# ESP8266_MegaD_v0_9.net
KiCad netlist of a schematic drawn in EAGLE
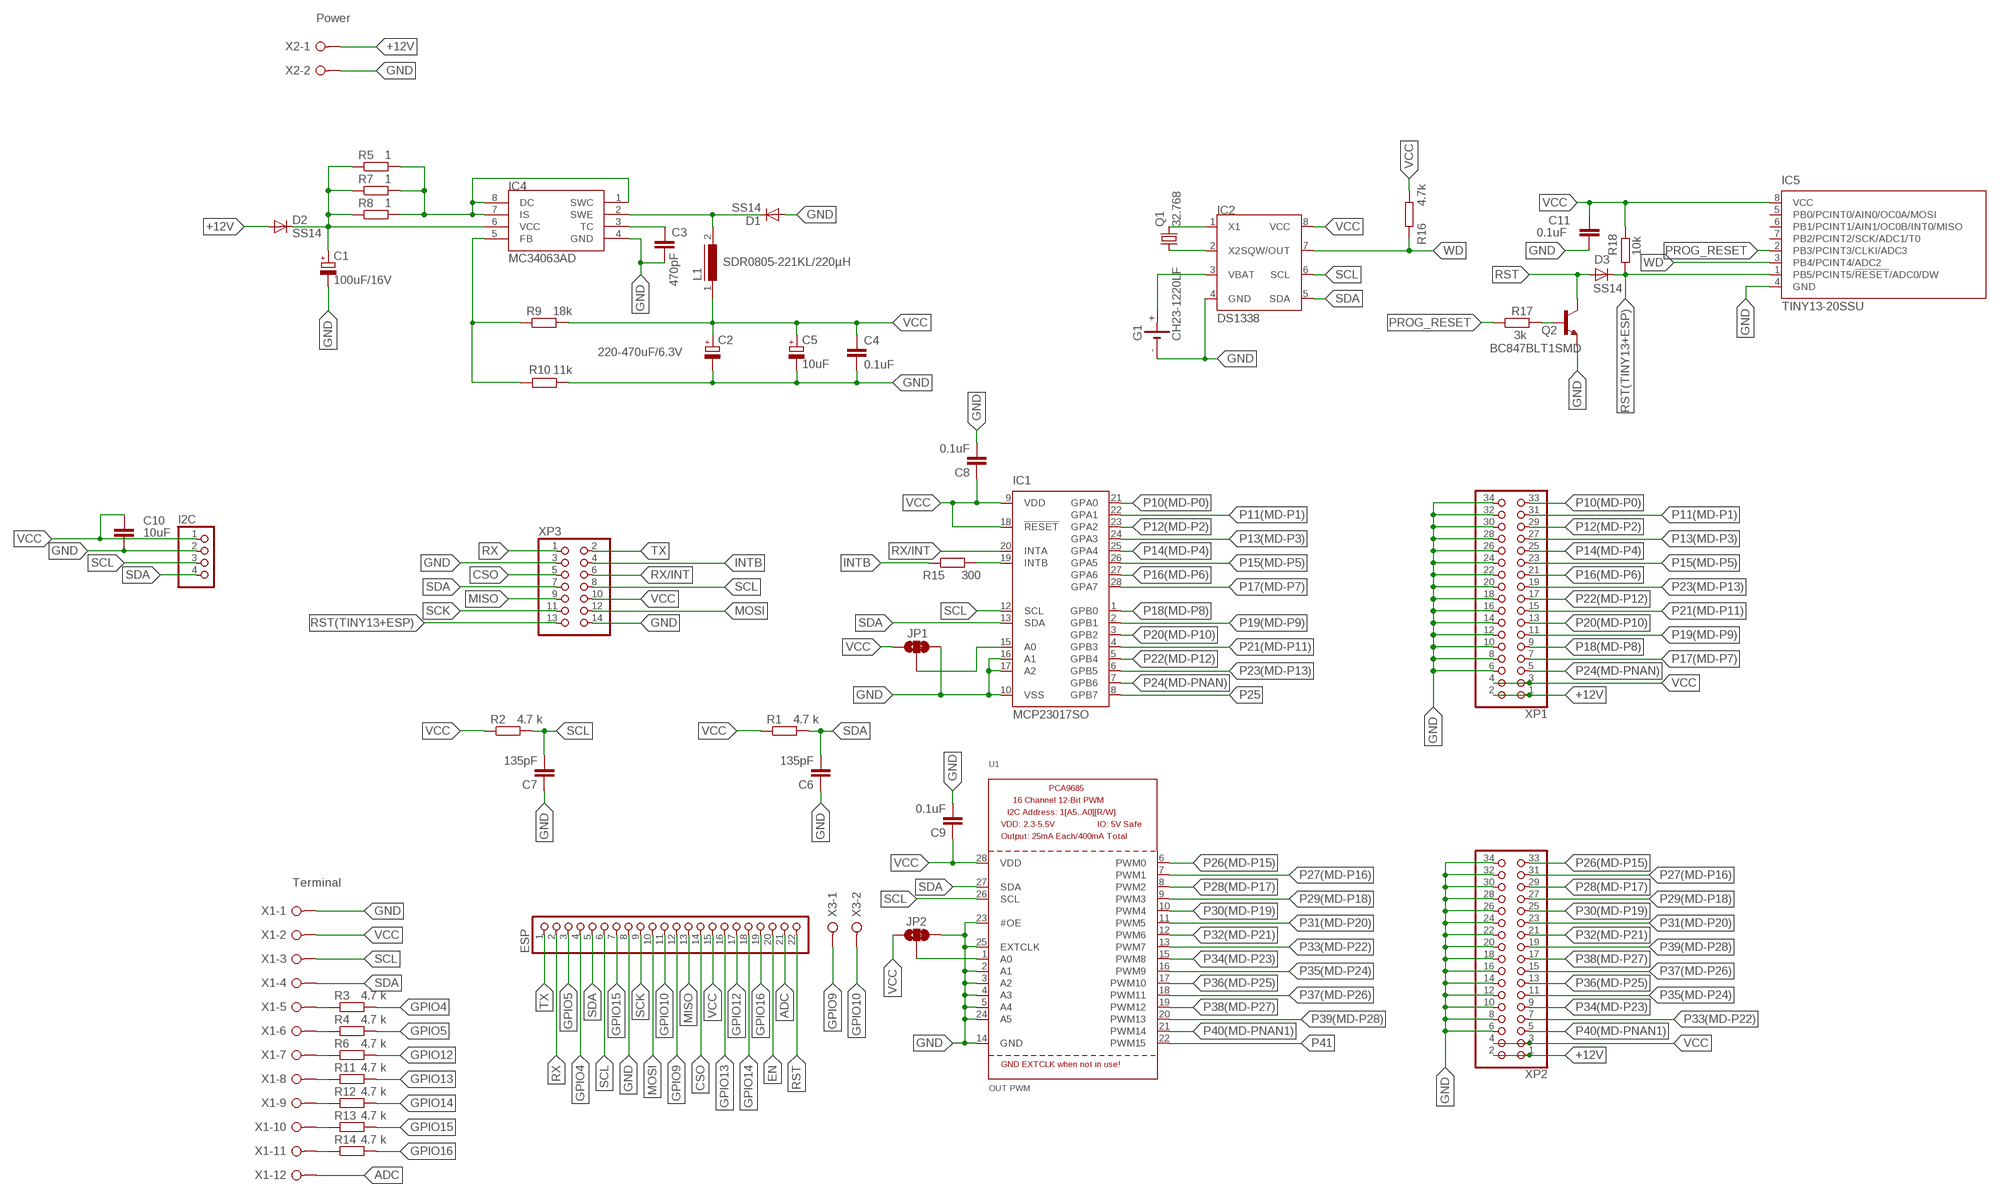
[diagram p0: schematic, sheet 1]

(export (version "E")
  (design (tool "Eeschema 10.0.6"))
  (components
    (comp (ref "C1")
      (value "100uF/16V")
      (footprint "eagle-import:140CLH-0810")
      (libsource (lib "eagle-import") (part "CPOL-EU140CLH-0810"))
    )
    (comp (ref "C2")
      (value "220-470uF/6.3V")
      (footprint "eagle-import:140CLH-0810")
      (libsource (lib "eagle-import") (part "CPOL-EU140CLH-0810"))
    )
    (comp (ref "C3")
      (value "470pF")
      (footprint "eagle-import:C1206")
      (libsource (lib "eagle-import") (part "C-EUC1206"))
    )
    (comp (ref "C4")
      (value "0.1uF")
      (footprint "eagle-import:C1206")
      (libsource (lib "eagle-import") (part "C-EUC1206"))
    )
    (comp (ref "C5")
      (value "10uF")
      (footprint "eagle-import:C_6032-28R")
      (libsource (lib "eagle-import") (part "CPOL-EUC/6032-28R"))
    )
    (comp (ref "C6")
      (value "135pF")
      (footprint "eagle-import:C1206")
      (libsource (lib "eagle-import") (part "C-EUC1206"))
    )
    (comp (ref "C7")
      (value "135pF")
      (footprint "eagle-import:C1206")
      (libsource (lib "eagle-import") (part "C-EUC1206"))
    )
    (comp (ref "C8")
      (value "0.1uF")
      (footprint "eagle-import:C1206")
      (libsource (lib "eagle-import") (part "C-EUC1206"))
    )
    (comp (ref "C9")
      (value "0.1uF")
      (footprint "eagle-import:C1206")
      (libsource (lib "eagle-import") (part "C-EUC1206"))
    )
    (comp (ref "C10")
      (value "10uF")
      (footprint "eagle-import:C1206")
      (libsource (lib "eagle-import") (part "C-EUC1206"))
    )
    (comp (ref "C11")
      (value "0.1uF")
      (footprint "eagle-import:C1206")
      (libsource (lib "eagle-import") (part "C-EUC1206"))
    )
    (comp (ref "D1")
      (value "SS14")
      (footprint "eagle-import:SMA")
      (libsource (lib "eagle-import") (part "S1M"))
    )
    (comp (ref "D2")
      (value "SS14")
      (footprint "eagle-import:SMA")
      (libsource (lib "eagle-import") (part "S1M"))
    )
    (comp (ref "D3")
      (value "SS14")
      (footprint "eagle-import:SMA")
      (libsource (lib "eagle-import") (part "S1M"))
    )
    (comp (ref "ESP")
      (value "PINHD-1X22")
      (footprint "eagle-import:1X22")
      (libsource (lib "eagle-import") (part "PINHD-1X22"))
    )
    (comp (ref "G1")
      (value "CH23-1220LF")
      (footprint "eagle-import:CH23-1220LF")
      (libsource (lib "eagle-import") (part "CH23-1220LF"))
    )
    (comp (ref "I2C")
      (value "PINHD-1X4")
      (footprint "eagle-import:1X04")
      (libsource (lib "eagle-import") (part "PINHD-1X4"))
    )
    (comp (ref "IC1")
      (value "MCP23017SO")
      (footprint "eagle-import:SO28W")
      (fields (field (name "MF") "MICROCHIP") (field (name "MPN") "MCP23017-E/SO"))
      (libsource (lib "eagle-import") (part "MCP23017SO"))
    )
    (comp (ref "IC2")
      (value "DS1338")
      (footprint "eagle-import:SOIC-8")
      (libsource (lib "eagle-import") (part "DS1307"))
    )
    (comp (ref "IC4")
      (value "MC34063AD")
      (footprint "eagle-import:SOIC8")
      (libsource (lib "eagle-import") (part "MC34063AD"))
    )
    (comp (ref "IC5")
      (value "TINY13-20SSU")
      (footprint "eagle-import:8S1")
      (fields (field (name "MPN") "ATTINY13-20SSU"))
      (libsource (lib "eagle-import") (part "TINY13SSU-20"))
    )
    (comp (ref "JP1")
      (value "JUMPER-PAD-3-2OF3_NC_BY_TRACE_LARGE")
      (footprint "eagle-import:PAD-JUMPER-3-2OF3_NC_BY_TRACE_YES_SILK_LARGE")
      (libsource (lib "eagle-import") (part "JUMPER-PAD-3-2OF3_NC_BY_TRACE_LARGE"))
    )
    (comp (ref "JP2")
      (value "JUMPER-PAD-3-2OF3_NC_BY_TRACE_LARGE")
      (footprint "eagle-import:PAD-JUMPER-3-2OF3_NC_BY_TRACE_YES_SILK_LARGE")
      (libsource (lib "eagle-import") (part "JUMPER-PAD-3-2OF3_NC_BY_TRACE_LARGE"))
    )
    (comp (ref "L1")
      (value "SDR0805-221KL/220µH")
      (footprint "eagle-import:DR73")
      (libsource (lib "eagle-import") (part "DR73"))
    )
    (comp (ref "Q1")
      (value "32.768")
      (footprint "eagle-import:TC38H")
      (libsource (lib "eagle-import") (part "CRYSTALTC38H"))
    )
    (comp (ref "Q2")
      (value "BC847BLT1SMD")
      (footprint "eagle-import:SOT23")
      (libsource (lib "eagle-import") (part "BC847SMDBLT1"))
    )
    (comp (ref "R1")
      (value "4.7 k")
      (footprint "eagle-import:R1206")
      (libsource (lib "eagle-import") (part "R-EU_R1206"))
    )
    (comp (ref "R2")
      (value "4.7 k")
      (footprint "eagle-import:R1206")
      (libsource (lib "eagle-import") (part "R-EU_R1206"))
    )
    (comp (ref "R3")
      (value "4.7 k")
      (footprint "eagle-import:R1206")
      (libsource (lib "eagle-import") (part "R-EU_R1206"))
    )
    (comp (ref "R4")
      (value "4.7 k")
      (footprint "eagle-import:R1206")
      (libsource (lib "eagle-import") (part "R-EU_R1206"))
    )
    (comp (ref "R5")
      (value "1")
      (footprint "eagle-import:R1206")
      (libsource (lib "eagle-import") (part "R-EU_R1206"))
    )
    (comp (ref "R6")
      (value "4.7 k")
      (footprint "eagle-import:R1206")
      (libsource (lib "eagle-import") (part "R-EU_R1206"))
    )
    (comp (ref "R7")
      (value "1")
      (footprint "eagle-import:R1206")
      (libsource (lib "eagle-import") (part "R-EU_R1206"))
    )
    (comp (ref "R8")
      (value "1")
      (footprint "eagle-import:R1206")
      (libsource (lib "eagle-import") (part "R-EU_R1206"))
    )
    (comp (ref "R9")
      (value "18k")
      (footprint "eagle-import:R1206")
      (libsource (lib "eagle-import") (part "R-EU_R1206"))
    )
    (comp (ref "R10")
      (value "11k")
      (footprint "eagle-import:R1206")
      (libsource (lib "eagle-import") (part "R-EU_R1206"))
    )
    (comp (ref "R11")
      (value "4.7 k")
      (footprint "eagle-import:R1206")
      (libsource (lib "eagle-import") (part "R-EU_R1206"))
    )
    (comp (ref "R12")
      (value "4.7 k")
      (footprint "eagle-import:R1206")
      (libsource (lib "eagle-import") (part "R-EU_R1206"))
    )
    (comp (ref "R13")
      (value "4.7 k")
      (footprint "eagle-import:R1206")
      (libsource (lib "eagle-import") (part "R-EU_R1206"))
    )
    (comp (ref "R14")
      (value "4.7 k")
      (footprint "eagle-import:R1206")
      (libsource (lib "eagle-import") (part "R-EU_R1206"))
    )
    (comp (ref "R15")
      (value "300")
      (footprint "eagle-import:R1206")
      (libsource (lib "eagle-import") (part "R-EU_R1206"))
    )
    (comp (ref "R16")
      (value "4.7k")
      (footprint "eagle-import:R1206")
      (libsource (lib "eagle-import") (part "R-EU_R1206"))
    )
    (comp (ref "R17")
      (value "3k")
      (footprint "eagle-import:R1206")
      (libsource (lib "eagle-import") (part "R-EU_R1206"))
    )
    (comp (ref "R18")
      (value "10k")
      (footprint "eagle-import:R1206")
      (libsource (lib "eagle-import") (part "R-EU_R1206"))
    )
    (comp (ref "U1")
      (value "OUT PWM")
      (footprint "eagle-import:TSSOP28")
      (libsource (lib "eagle-import") (part "PCA9685"))
    )
    (comp (ref "X1")
      (value "Terminal")
      (footprint "eagle-import:W237-12P")
      (libsource (lib "eagle-import") (part "W237-12P"))
    )
    (comp (ref "X2")
      (value "Power")
      (footprint "eagle-import:W237-132")
      (libsource (lib "eagle-import") (part "W237-02P"))
    )
    (comp (ref "X3")
      (value "W237-02P")
      (footprint "eagle-import:W237-132")
      (libsource (lib "eagle-import") (part "W237-02P"))
    )
    (comp (ref "XP1")
      (value "PINHD-2X17/90")
      (footprint "eagle-import:2X17_90")
      (libsource (lib "eagle-import") (part "PINHD-2X17/90"))
    )
    (comp (ref "XP2")
      (value "PINHD-2X17")
      (footprint "eagle-import:2X17")
      (libsource (lib "eagle-import") (part "PINHD-2X17"))
    )
    (comp (ref "XP3")
      (value "PINHD-2X7")
      (footprint "eagle-import:2X07")
      (libsource (lib "eagle-import") (part "PINHD-2X7"))
    )
  )
  (nets
    (net (code "1") (name "+12V") (class "Default")
      (node (ref "D2") (pin "A") (pinfunction "A_A") (pintype "passive"))
      (node (ref "X2") (pin "1") (pinfunction "KL_1") (pintype "passive"))
      (node (ref "XP1") (pin "1") (pinfunction "1_1") (pintype "passive"))
      (node (ref "XP1") (pin "2") (pinfunction "2_2") (pintype "passive"))
      (node (ref "XP2") (pin "1") (pinfunction "1_1") (pintype "passive"))
      (node (ref "XP2") (pin "2") (pinfunction "2_2") (pintype "passive"))
    )
    (net (code "2") (name "ADC") (class "Default")
      (node (ref "ESP") (pin "21") (pinfunction "21_21") (pintype "passive"))
      (node (ref "X1") (pin "12") (pinfunction "KL_12") (pintype "passive"))
    )
    (net (code "3") (name "CSO") (class "Default")
      (node (ref "ESP") (pin "14") (pinfunction "14_14") (pintype "passive"))
      (node (ref "XP3") (pin "5") (pinfunction "5_5") (pintype "passive"))
    )
    (net (code "4") (name "EN") (class "Default")
      (node (ref "ESP") (pin "20") (pinfunction "20_20") (pintype "passive"))
    )
    (net (code "5") (name "GND") (class "Default")
      (node (ref "C1") (pin "-") (pinfunction "-_-") (pintype "passive"))
      (node (ref "C10") (pin "1") (pinfunction "1_1") (pintype "passive"))
      (node (ref "C11") (pin "2") (pinfunction "2_2") (pintype "passive"))
      (node (ref "C2") (pin "-") (pinfunction "-_-") (pintype "passive"))
      (node (ref "C3") (pin "2") (pinfunction "2_2") (pintype "passive"))
      (node (ref "C4") (pin "2") (pinfunction "2_2") (pintype "passive"))
      (node (ref "C5") (pin "-") (pinfunction "-_-") (pintype "passive"))
      (node (ref "C6") (pin "1") (pinfunction "1_1") (pintype "passive"))
      (node (ref "C7") (pin "1") (pinfunction "1_1") (pintype "passive"))
      (node (ref "C8") (pin "2") (pinfunction "2_2") (pintype "passive"))
      (node (ref "C9") (pin "2") (pinfunction "2_2") (pintype "passive"))
      (node (ref "D1") (pin "A") (pinfunction "A_A") (pintype "passive"))
      (node (ref "ESP") (pin "8") (pinfunction "8_8") (pintype "passive"))
      (node (ref "G1") (pin "-") (pinfunction "-_-") (pintype "passive"))
      (node (ref "I2C") (pin "2") (pinfunction "2_2") (pintype "passive"))
      (node (ref "IC1") (pin "10") (pinfunction "VSS_10") (pintype "power_in"))
      (node (ref "IC1") (pin "16") (pinfunction "A1_16") (pintype "input"))
      (node (ref "IC1") (pin "17") (pinfunction "A2_17") (pintype "input"))
      (node (ref "IC2") (pin "4") (pinfunction "GND_4") (pintype "power_in"))
      (node (ref "IC4") (pin "4") (pinfunction "GND_4") (pintype "passive"))
      (node (ref "IC5") (pin "4") (pinfunction "GND_4") (pintype "power_in"))
      (node (ref "JP1") (pin "3") (pinfunction "3_3") (pintype "passive"))
      (node (ref "JP2") (pin "3") (pinfunction "3_3") (pintype "passive"))
      (node (ref "Q2") (pin "2") (pinfunction "E_2") (pintype "passive"))
      (node (ref "R10") (pin "1") (pinfunction "1_1") (pintype "passive"))
      (node (ref "U1") (pin "14") (pinfunction "GND_14") (pintype "power_in"))
      (node (ref "U1") (pin "2") (pinfunction "A1_2") (pintype "bidirectional"))
      (node (ref "U1") (pin "23") (pinfunction "#OE_23") (pintype "input"))
      (node (ref "U1") (pin "24") (pinfunction "A5_24") (pintype "bidirectional"))
      (node (ref "U1") (pin "25") (pinfunction "EXTCLK_25") (pintype "input"))
      (node (ref "U1") (pin "3") (pinfunction "A2_3") (pintype "bidirectional"))
      (node (ref "U1") (pin "4") (pinfunction "A3_4") (pintype "bidirectional"))
      (node (ref "U1") (pin "5") (pinfunction "A4_5") (pintype "bidirectional"))
      (node (ref "X1") (pin "1") (pinfunction "KL_1") (pintype "passive"))
      (node (ref "X2") (pin "2") (pinfunction "KL_2") (pintype "passive"))
      (node (ref "XP1") (pin "10") (pinfunction "10_10") (pintype "passive"))
      (node (ref "XP1") (pin "12") (pinfunction "12_12") (pintype "passive"))
      (node (ref "XP1") (pin "14") (pinfunction "14_14") (pintype "passive"))
      (node (ref "XP1") (pin "16") (pinfunction "16_16") (pintype "passive"))
      (node (ref "XP1") (pin "18") (pinfunction "18_18") (pintype "passive"))
      (node (ref "XP1") (pin "20") (pinfunction "20_20") (pintype "passive"))
      (node (ref "XP1") (pin "22") (pinfunction "22_22") (pintype "passive"))
      (node (ref "XP1") (pin "24") (pinfunction "24_24") (pintype "passive"))
      (node (ref "XP1") (pin "26") (pinfunction "26_26") (pintype "passive"))
      (node (ref "XP1") (pin "28") (pinfunction "28_28") (pintype "passive"))
      (node (ref "XP1") (pin "30") (pinfunction "30_30") (pintype "passive"))
      (node (ref "XP1") (pin "32") (pinfunction "32_32") (pintype "passive"))
      (node (ref "XP1") (pin "34") (pinfunction "34_34") (pintype "passive"))
      (node (ref "XP1") (pin "6") (pinfunction "6_6") (pintype "passive"))
      (node (ref "XP1") (pin "8") (pinfunction "8_8") (pintype "passive"))
      (node (ref "XP2") (pin "10") (pinfunction "10_10") (pintype "passive"))
      (node (ref "XP2") (pin "12") (pinfunction "12_12") (pintype "passive"))
      (node (ref "XP2") (pin "14") (pinfunction "14_14") (pintype "passive"))
      (node (ref "XP2") (pin "16") (pinfunction "16_16") (pintype "passive"))
      (node (ref "XP2") (pin "18") (pinfunction "18_18") (pintype "passive"))
      (node (ref "XP2") (pin "20") (pinfunction "20_20") (pintype "passive"))
      (node (ref "XP2") (pin "22") (pinfunction "22_22") (pintype "passive"))
      (node (ref "XP2") (pin "24") (pinfunction "24_24") (pintype "passive"))
      (node (ref "XP2") (pin "26") (pinfunction "26_26") (pintype "passive"))
      (node (ref "XP2") (pin "28") (pinfunction "28_28") (pintype "passive"))
      (node (ref "XP2") (pin "30") (pinfunction "30_30") (pintype "passive"))
      (node (ref "XP2") (pin "32") (pinfunction "32_32") (pintype "passive"))
      (node (ref "XP2") (pin "34") (pinfunction "34_34") (pintype "passive"))
      (node (ref "XP2") (pin "6") (pinfunction "6_6") (pintype "passive"))
      (node (ref "XP2") (pin "8") (pinfunction "8_8") (pintype "passive"))
      (node (ref "XP3") (pin "14") (pinfunction "14_14") (pintype "passive"))
      (node (ref "XP3") (pin "3") (pinfunction "3_3") (pintype "passive"))
    )
    (net (code "6") (name "GPIO4") (class "Default")
      (node (ref "ESP") (pin "4") (pinfunction "4_4") (pintype "passive"))
      (node (ref "R3") (pin "2") (pinfunction "2_2") (pintype "passive"))
    )
    (net (code "7") (name "GPIO5") (class "Default")
      (node (ref "ESP") (pin "3") (pinfunction "3_3") (pintype "passive"))
      (node (ref "R4") (pin "2") (pinfunction "2_2") (pintype "passive"))
    )
    (net (code "8") (name "GPIO9") (class "Default")
      (node (ref "ESP") (pin "12") (pinfunction "12_12") (pintype "passive"))
      (node (ref "X3") (pin "1") (pinfunction "KL_1") (pintype "passive"))
    )
    (net (code "9") (name "GPIO10") (class "Default")
      (node (ref "ESP") (pin "11") (pinfunction "11_11") (pintype "passive"))
      (node (ref "X3") (pin "2") (pinfunction "KL_2") (pintype "passive"))
    )
    (net (code "10") (name "GPIO12") (class "Default")
      (node (ref "ESP") (pin "17") (pinfunction "17_17") (pintype "passive"))
      (node (ref "R6") (pin "2") (pinfunction "2_2") (pintype "passive"))
    )
    (net (code "11") (name "GPIO13") (class "Default")
      (node (ref "ESP") (pin "16") (pinfunction "16_16") (pintype "passive"))
      (node (ref "R11") (pin "2") (pinfunction "2_2") (pintype "passive"))
    )
    (net (code "12") (name "GPIO14") (class "Default")
      (node (ref "ESP") (pin "18") (pinfunction "18_18") (pintype "passive"))
      (node (ref "R12") (pin "2") (pinfunction "2_2") (pintype "passive"))
    )
    (net (code "13") (name "GPIO15") (class "Default")
      (node (ref "ESP") (pin "7") (pinfunction "7_7") (pintype "passive"))
      (node (ref "R13") (pin "2") (pinfunction "2_2") (pintype "passive"))
    )
    (net (code "14") (name "GPIO16") (class "Default")
      (node (ref "ESP") (pin "19") (pinfunction "19_19") (pintype "passive"))
      (node (ref "R14") (pin "2") (pinfunction "2_2") (pintype "passive"))
    )
    (net (code "15") (name "INTB") (class "Default")
      (node (ref "R15") (pin "1") (pinfunction "1_1") (pintype "passive"))
      (node (ref "XP3") (pin "4") (pinfunction "4_4") (pintype "passive"))
    )
    (net (code "16") (name "MISO") (class "Default")
      (node (ref "ESP") (pin "13") (pinfunction "13_13") (pintype "passive"))
      (node (ref "XP3") (pin "9") (pinfunction "9_9") (pintype "passive"))
    )
    (net (code "17") (name "MOSI") (class "Default")
      (node (ref "ESP") (pin "10") (pinfunction "10_10") (pintype "passive"))
      (node (ref "XP3") (pin "12") (pinfunction "12_12") (pintype "passive"))
    )
    (net (code "18") (name "Net-(IC1-A0)") (class "Default")
      (node (ref "IC1") (pin "15") (pinfunction "A0_15") (pintype "input"))
      (node (ref "JP1") (pin "2") (pinfunction "2_2") (pintype "passive"))
    )
    (net (code "19") (name "Net-(IC1-INTB)") (class "Default")
      (node (ref "IC1") (pin "19") (pinfunction "INTB_19") (pintype "output"))
      (node (ref "R15") (pin "2") (pinfunction "2_2") (pintype "passive"))
    )
    (net (code "20") (name "Net-(IC2-VBAT)") (class "Default")
      (node (ref "G1") (pin "+") (pinfunction "+_+") (pintype "passive"))
      (node (ref "IC2") (pin "3") (pinfunction "VBAT_3") (pintype "power_in"))
    )
    (net (code "21") (name "Net-(IC2-X1)") (class "Default")
      (node (ref "IC2") (pin "1") (pinfunction "X1_1") (pintype "input"))
      (node (ref "Q1") (pin "2") (pinfunction "2_2") (pintype "passive"))
    )
    (net (code "22") (name "Net-(IC2-X2)") (class "Default")
      (node (ref "IC2") (pin "2") (pinfunction "X2_2") (pintype "output"))
      (node (ref "Q1") (pin "1") (pinfunction "1_1") (pintype "passive"))
    )
    (net (code "23") (name "Net-(IC4-DC)") (class "Default")
      (node (ref "IC4") (pin "1") (pinfunction "SWC_1") (pintype "passive"))
      (node (ref "IC4") (pin "7") (pinfunction "IS_7") (pintype "passive"))
      (node (ref "IC4") (pin "8") (pinfunction "DC_8") (pintype "passive"))
      (node (ref "R5") (pin "2") (pinfunction "2_2") (pintype "passive"))
      (node (ref "R7") (pin "2") (pinfunction "2_2") (pintype "passive"))
      (node (ref "R8") (pin "2") (pinfunction "2_2") (pintype "passive"))
    )
    (net (code "24") (name "Net-(IC4-FB)") (class "Default")
      (node (ref "IC4") (pin "5") (pinfunction "FB_5") (pintype "passive"))
      (node (ref "R10") (pin "2") (pinfunction "2_2") (pintype "passive"))
      (node (ref "R9") (pin "1") (pinfunction "1_1") (pintype "passive"))
    )
    (net (code "25") (name "Net-(IC4-SWE)") (class "Default")
      (node (ref "D1") (pin "C") (pinfunction "C_C") (pintype "passive"))
      (node (ref "IC4") (pin "2") (pinfunction "SWE_2") (pintype "passive"))
      (node (ref "L1") (pin "2") (pinfunction "2_2") (pintype "passive"))
    )
    (net (code "26") (name "Net-(IC4-TC)") (class "Default")
      (node (ref "C3") (pin "1") (pinfunction "1_1") (pintype "passive"))
      (node (ref "IC4") (pin "3") (pinfunction "TC_3") (pintype "passive"))
    )
    (net (code "27") (name "Net-(IC4-VCC)") (class "Default")
      (node (ref "C1") (pin "+") (pinfunction "+_+") (pintype "passive"))
      (node (ref "D2") (pin "C") (pinfunction "C_C") (pintype "passive"))
      (node (ref "IC4") (pin "6") (pinfunction "VCC_6") (pintype "passive"))
      (node (ref "R5") (pin "1") (pinfunction "1_1") (pintype "passive"))
      (node (ref "R7") (pin "1") (pinfunction "1_1") (pintype "passive"))
      (node (ref "R8") (pin "1") (pinfunction "1_1") (pintype "passive"))
    )
    (net (code "28") (name "Net-(Q2-B)") (class "Default")
      (node (ref "Q2") (pin "1") (pinfunction "B_1") (pintype "passive"))
      (node (ref "R17") (pin "2") (pinfunction "2_2") (pintype "passive"))
    )
    (net (code "29") (name "Net-(U1-A0)") (class "Default")
      (node (ref "JP2") (pin "2") (pinfunction "2_2") (pintype "passive"))
      (node (ref "U1") (pin "1") (pinfunction "A0_1") (pintype "bidirectional"))
    )
    (net (code "30") (name "Net-(X1B-KL)") (class "Default")
      (node (ref "R13") (pin "1") (pinfunction "1_1") (pintype "passive"))
      (node (ref "X1") (pin "10") (pinfunction "KL_10") (pintype "passive"))
    )
    (net (code "31") (name "Net-(X1C-KL)") (class "Default")
      (node (ref "R14") (pin "1") (pinfunction "1_1") (pintype "passive"))
      (node (ref "X1") (pin "11") (pinfunction "KL_11") (pintype "passive"))
    )
    (net (code "32") (name "Net-(X1H-KL)") (class "Default")
      (node (ref "R3") (pin "1") (pinfunction "1_1") (pintype "passive"))
      (node (ref "X1") (pin "5") (pinfunction "KL_5") (pintype "passive"))
    )
    (net (code "33") (name "Net-(X1I-KL)") (class "Default")
      (node (ref "R4") (pin "1") (pinfunction "1_1") (pintype "passive"))
      (node (ref "X1") (pin "6") (pinfunction "KL_6") (pintype "passive"))
    )
    (net (code "34") (name "Net-(X1J-KL)") (class "Default")
      (node (ref "R6") (pin "1") (pinfunction "1_1") (pintype "passive"))
      (node (ref "X1") (pin "7") (pinfunction "KL_7") (pintype "passive"))
    )
    (net (code "35") (name "Net-(X1K-KL)") (class "Default")
      (node (ref "R11") (pin "1") (pinfunction "1_1") (pintype "passive"))
      (node (ref "X1") (pin "8") (pinfunction "KL_8") (pintype "passive"))
    )
    (net (code "36") (name "Net-(X1L-KL)") (class "Default")
      (node (ref "R12") (pin "1") (pinfunction "1_1") (pintype "passive"))
      (node (ref "X1") (pin "9") (pinfunction "KL_9") (pintype "passive"))
    )
    (net (code "37") (name "P10(MD-P0)") (class "Default")
      (node (ref "IC1") (pin "21") (pinfunction "GPA0_21") (pintype "bidirectional"))
      (node (ref "XP1") (pin "33") (pinfunction "33_33") (pintype "passive"))
    )
    (net (code "38") (name "P11(MD-P1)") (class "Default")
      (node (ref "IC1") (pin "22") (pinfunction "GPA1_22") (pintype "bidirectional"))
      (node (ref "XP1") (pin "31") (pinfunction "31_31") (pintype "passive"))
    )
    (net (code "39") (name "P12(MD-P2)") (class "Default")
      (node (ref "IC1") (pin "23") (pinfunction "GPA2_23") (pintype "bidirectional"))
      (node (ref "XP1") (pin "29") (pinfunction "29_29") (pintype "passive"))
    )
    (net (code "40") (name "P13(MD-P3)") (class "Default")
      (node (ref "IC1") (pin "24") (pinfunction "GPA3_24") (pintype "bidirectional"))
      (node (ref "XP1") (pin "27") (pinfunction "27_27") (pintype "passive"))
    )
    (net (code "41") (name "P14(MD-P4)") (class "Default")
      (node (ref "IC1") (pin "25") (pinfunction "GPA4_25") (pintype "bidirectional"))
      (node (ref "XP1") (pin "25") (pinfunction "25_25") (pintype "passive"))
    )
    (net (code "42") (name "P15(MD-P5)") (class "Default")
      (node (ref "IC1") (pin "26") (pinfunction "GPA5_26") (pintype "bidirectional"))
      (node (ref "XP1") (pin "23") (pinfunction "23_23") (pintype "passive"))
    )
    (net (code "43") (name "P16(MD-P6)") (class "Default")
      (node (ref "IC1") (pin "27") (pinfunction "GPA6_27") (pintype "bidirectional"))
      (node (ref "XP1") (pin "21") (pinfunction "21_21") (pintype "passive"))
    )
    (net (code "44") (name "P17(MD-P7)") (class "Default")
      (node (ref "IC1") (pin "28") (pinfunction "GPA7_28") (pintype "bidirectional"))
      (node (ref "XP1") (pin "7") (pinfunction "7_7") (pintype "passive"))
    )
    (net (code "45") (name "P18(MD-P8)") (class "Default")
      (node (ref "IC1") (pin "1") (pinfunction "GPB0_1") (pintype "bidirectional"))
      (node (ref "XP1") (pin "9") (pinfunction "9_9") (pintype "passive"))
    )
    (net (code "46") (name "P19(MD-P9)") (class "Default")
      (node (ref "IC1") (pin "2") (pinfunction "GPB1_2") (pintype "bidirectional"))
      (node (ref "XP1") (pin "11") (pinfunction "11_11") (pintype "passive"))
    )
    (net (code "47") (name "P20(MD-P10)") (class "Default")
      (node (ref "IC1") (pin "3") (pinfunction "GPB2_3") (pintype "bidirectional"))
      (node (ref "XP1") (pin "13") (pinfunction "13_13") (pintype "passive"))
    )
    (net (code "48") (name "P21(MD-P11)") (class "Default")
      (node (ref "IC1") (pin "4") (pinfunction "GPB3_4") (pintype "bidirectional"))
      (node (ref "XP1") (pin "15") (pinfunction "15_15") (pintype "passive"))
    )
    (net (code "49") (name "P22(MD-P12)") (class "Default")
      (node (ref "IC1") (pin "5") (pinfunction "GPB4_5") (pintype "bidirectional"))
      (node (ref "XP1") (pin "17") (pinfunction "17_17") (pintype "passive"))
    )
    (net (code "50") (name "P23(MD-P13)") (class "Default")
      (node (ref "IC1") (pin "6") (pinfunction "GPB5_6") (pintype "bidirectional"))
      (node (ref "XP1") (pin "19") (pinfunction "19_19") (pintype "passive"))
    )
    (net (code "51") (name "P24(MD-PNAN)") (class "Default")
      (node (ref "IC1") (pin "7") (pinfunction "GPB6_7") (pintype "bidirectional"))
      (node (ref "XP1") (pin "5") (pinfunction "5_5") (pintype "passive"))
    )
    (net (code "52") (name "P25") (class "Default")
      (node (ref "IC1") (pin "8") (pinfunction "GPB7_8") (pintype "bidirectional"))
    )
    (net (code "53") (name "P26(MD-P15)") (class "Default")
      (node (ref "U1") (pin "6") (pinfunction "PWM0_6") (pintype "output"))
      (node (ref "XP2") (pin "33") (pinfunction "33_33") (pintype "passive"))
    )
    (net (code "54") (name "P27(MD-P16)") (class "Default")
      (node (ref "U1") (pin "7") (pinfunction "PWM1_7") (pintype "output"))
      (node (ref "XP2") (pin "31") (pinfunction "31_31") (pintype "passive"))
    )
    (net (code "55") (name "P28(MD-P17)") (class "Default")
      (node (ref "U1") (pin "8") (pinfunction "PWM2_8") (pintype "output"))
      (node (ref "XP2") (pin "29") (pinfunction "29_29") (pintype "passive"))
    )
    (net (code "56") (name "P29(MD-P18)") (class "Default")
      (node (ref "U1") (pin "9") (pinfunction "PWM3_9") (pintype "output"))
      (node (ref "XP2") (pin "27") (pinfunction "27_27") (pintype "passive"))
    )
    (net (code "57") (name "P30(MD-P19)") (class "Default")
      (node (ref "U1") (pin "10") (pinfunction "PWM4_10") (pintype "output"))
      (node (ref "XP2") (pin "25") (pinfunction "25_25") (pintype "passive"))
    )
    (net (code "58") (name "P31(MD-P20)") (class "Default")
      (node (ref "U1") (pin "11") (pinfunction "PWM5_11") (pintype "output"))
      (node (ref "XP2") (pin "23") (pinfunction "23_23") (pintype "passive"))
    )
    (net (code "59") (name "P32(MD-P21)") (class "Default")
      (node (ref "U1") (pin "12") (pinfunction "PWM6_12") (pintype "output"))
      (node (ref "XP2") (pin "21") (pinfunction "21_21") (pintype "passive"))
    )
    (net (code "60") (name "P33(MD-P22)") (class "Default")
      (node (ref "U1") (pin "13") (pinfunction "PWM7_13") (pintype "output"))
      (node (ref "XP2") (pin "7") (pinfunction "7_7") (pintype "passive"))
    )
    (net (code "61") (name "P34(MD-P23)") (class "Default")
      (node (ref "U1") (pin "15") (pinfunction "PWM8_15") (pintype "output"))
      (node (ref "XP2") (pin "9") (pinfunction "9_9") (pintype "passive"))
    )
    (net (code "62") (name "P35(MD-P24)") (class "Default")
      (node (ref "U1") (pin "16") (pinfunction "PWM9_16") (pintype "output"))
      (node (ref "XP2") (pin "11") (pinfunction "11_11") (pintype "passive"))
    )
    (net (code "63") (name "P36(MD-P25)") (class "Default")
      (node (ref "U1") (pin "17") (pinfunction "PWM10_17") (pintype "output"))
      (node (ref "XP2") (pin "13") (pinfunction "13_13") (pintype "passive"))
    )
    (net (code "64") (name "P37(MD-P26)") (class "Default")
      (node (ref "U1") (pin "18") (pinfunction "PWM11_18") (pintype "output"))
      (node (ref "XP2") (pin "15") (pinfunction "15_15") (pintype "passive"))
    )
    (net (code "65") (name "P38(MD-P27)") (class "Default")
      (node (ref "U1") (pin "19") (pinfunction "PWM12_19") (pintype "output"))
      (node (ref "XP2") (pin "17") (pinfunction "17_17") (pintype "passive"))
    )
    (net (code "66") (name "P39(MD-P28)") (class "Default")
      (node (ref "U1") (pin "20") (pinfunction "PWM13_20") (pintype "output"))
      (node (ref "XP2") (pin "19") (pinfunction "19_19") (pintype "passive"))
    )
    (net (code "67") (name "P40(MD-PNAN1)") (class "Default")
      (node (ref "U1") (pin "21") (pinfunction "PWM14_21") (pintype "output"))
      (node (ref "XP2") (pin "5") (pinfunction "5_5") (pintype "passive"))
    )
    (net (code "68") (name "P41") (class "Default")
      (node (ref "U1") (pin "22") (pinfunction "PWM15_22") (pintype "output"))
    )
    (net (code "69") (name "PROG_RESET") (class "Default")
      (node (ref "IC5") (pin "2") (pinfunction "PB3/PCINT3/CLKI/ADC3_2") (pintype "bidirectional"))
      (node (ref "R17") (pin "1") (pinfunction "1_1") (pintype "passive"))
    )
    (net (code "70") (name "RST") (class "Default")
      (node (ref "D3") (pin "A") (pinfunction "A_A") (pintype "passive"))
      (node (ref "ESP") (pin "22") (pinfunction "22_22") (pintype "passive"))
      (node (ref "Q2") (pin "3") (pinfunction "C_3") (pintype "passive"))
    )
    (net (code "71") (name "RST(TINY13+ESP)") (class "Default")
      (node (ref "D3") (pin "C") (pinfunction "C_C") (pintype "passive"))
      (node (ref "IC5") (pin "1") (pinfunction "PB5/PCINT5/~{RESET}/ADC0/DW_1") (pintype "bidirectional"))
      (node (ref "R18") (pin "1") (pinfunction "1_1") (pintype "passive"))
      (node (ref "XP3") (pin "13") (pinfunction "13_13") (pintype "passive"))
    )
    (net (code "72") (name "RX") (class "Default")
      (node (ref "ESP") (pin "2") (pinfunction "2_2") (pintype "passive"))
      (node (ref "XP3") (pin "1") (pinfunction "1_1") (pintype "passive"))
    )
    (net (code "73") (name "RX{slash}INT") (class "Default")
      (node (ref "IC1") (pin "20") (pinfunction "INTA_20") (pintype "output"))
      (node (ref "XP3") (pin "6") (pinfunction "6_6") (pintype "passive"))
    )
    (net (code "74") (name "SCK") (class "Default")
      (node (ref "ESP") (pin "9") (pinfunction "9_9") (pintype "passive"))
      (node (ref "XP3") (pin "11") (pinfunction "11_11") (pintype "passive"))
    )
    (net (code "75") (name "SCL") (class "Default")
      (node (ref "C7") (pin "2") (pinfunction "2_2") (pintype "passive"))
      (node (ref "ESP") (pin "6") (pinfunction "6_6") (pintype "passive"))
      (node (ref "I2C") (pin "3") (pinfunction "3_3") (pintype "passive"))
      (node (ref "IC1") (pin "12") (pinfunction "SCL_12") (pintype "input"))
      (node (ref "IC2") (pin "6") (pinfunction "SCL_6") (pintype "input"))
      (node (ref "R2") (pin "2") (pinfunction "2_2") (pintype "passive"))
      (node (ref "U1") (pin "26") (pinfunction "SCL_26") (pintype "bidirectional"))
      (node (ref "X1") (pin "3") (pinfunction "KL_3") (pintype "passive"))
      (node (ref "XP3") (pin "8") (pinfunction "8_8") (pintype "passive"))
    )
    (net (code "76") (name "SDA") (class "Default")
      (node (ref "C6") (pin "2") (pinfunction "2_2") (pintype "passive"))
      (node (ref "ESP") (pin "5") (pinfunction "5_5") (pintype "passive"))
      (node (ref "I2C") (pin "4") (pinfunction "4_4") (pintype "passive"))
      (node (ref "IC1") (pin "13") (pinfunction "SDA_13") (pintype "bidirectional"))
      (node (ref "IC2") (pin "5") (pinfunction "SDA_5") (pintype "bidirectional"))
      (node (ref "R1") (pin "2") (pinfunction "2_2") (pintype "passive"))
      (node (ref "U1") (pin "27") (pinfunction "SDA_27") (pintype "bidirectional"))
      (node (ref "X1") (pin "4") (pinfunction "KL_4") (pintype "passive"))
      (node (ref "XP3") (pin "7") (pinfunction "7_7") (pintype "passive"))
    )
    (net (code "77") (name "TX") (class "Default")
      (node (ref "ESP") (pin "1") (pinfunction "1_1") (pintype "passive"))
      (node (ref "XP3") (pin "2") (pinfunction "2_2") (pintype "passive"))
    )
    (net (code "78") (name "VCC") (class "Default")
      (node (ref "C10") (pin "2") (pinfunction "2_2") (pintype "passive"))
      (node (ref "C11") (pin "1") (pinfunction "1_1") (pintype "passive"))
      (node (ref "C2") (pin "+") (pinfunction "+_+") (pintype "passive"))
      (node (ref "C4") (pin "1") (pinfunction "1_1") (pintype "passive"))
      (node (ref "C5") (pin "+") (pinfunction "+_+") (pintype "passive"))
      (node (ref "C8") (pin "1") (pinfunction "1_1") (pintype "passive"))
      (node (ref "C9") (pin "1") (pinfunction "1_1") (pintype "passive"))
      (node (ref "ESP") (pin "15") (pinfunction "15_15") (pintype "passive"))
      (node (ref "I2C") (pin "1") (pinfunction "1_1") (pintype "passive"))
      (node (ref "IC1") (pin "18") (pinfunction "~{RESET}_18") (pintype "input"))
      (node (ref "IC1") (pin "9") (pinfunction "VDD_9") (pintype "power_in"))
      (node (ref "IC2") (pin "8") (pinfunction "VCC_8") (pintype "power_in"))
      (node (ref "IC5") (pin "8") (pinfunction "VCC_8") (pintype "power_in"))
      (node (ref "JP1") (pin "1") (pinfunction "1_1") (pintype "passive"))
      (node (ref "JP2") (pin "1") (pinfunction "1_1") (pintype "passive"))
      (node (ref "L1") (pin "1") (pinfunction "1_1") (pintype "passive"))
      (node (ref "R1") (pin "1") (pinfunction "1_1") (pintype "passive"))
      (node (ref "R16") (pin "2") (pinfunction "2_2") (pintype "passive"))
      (node (ref "R18") (pin "2") (pinfunction "2_2") (pintype "passive"))
      (node (ref "R2") (pin "1") (pinfunction "1_1") (pintype "passive"))
      (node (ref "R9") (pin "2") (pinfunction "2_2") (pintype "passive"))
      (node (ref "U1") (pin "28") (pinfunction "VDD_28") (pintype "power_in"))
      (node (ref "X1") (pin "2") (pinfunction "KL_2") (pintype "passive"))
      (node (ref "XP1") (pin "3") (pinfunction "3_3") (pintype "passive"))
      (node (ref "XP1") (pin "4") (pinfunction "4_4") (pintype "passive"))
      (node (ref "XP2") (pin "3") (pinfunction "3_3") (pintype "passive"))
      (node (ref "XP2") (pin "4") (pinfunction "4_4") (pintype "passive"))
      (node (ref "XP3") (pin "10") (pinfunction "10_10") (pintype "passive"))
    )
    (net (code "79") (name "WD") (class "Default")
      (node (ref "IC2") (pin "7") (pinfunction "SQW/OUT_7") (pintype "output"))
      (node (ref "IC5") (pin "3") (pinfunction "PB4/PCINT4/ADC2_3") (pintype "bidirectional"))
      (node (ref "R16") (pin "1") (pinfunction "1_1") (pintype "passive"))
    )
    (net (code "80") (name "unconnected-(IC5-PB0{slash}PCINT0{slash}AIN0{slash}OC0A{slash}MOSI-Pad5)") (class "Default")
      (node (ref "IC5") (pin "5") (pinfunction "PB0/PCINT0/AIN0/OC0A/MOSI_5") (pintype "bidirectional"))
    )
    (net (code "81") (name "unconnected-(IC5-PB1{slash}PCINT1{slash}AIN1{slash}OC0B{slash}INT0{slash}MISO-Pad6)") (class "Default")
      (node (ref "IC5") (pin "6") (pinfunction "PB1/PCINT1/AIN1/OC0B/INT0/MISO_6") (pintype "bidirectional"))
    )
    (net (code "82") (name "unconnected-(IC5-PB2{slash}PCINT2{slash}SCK{slash}ADC1{slash}T0-Pad7)") (class "Default")
      (node (ref "IC5") (pin "7") (pinfunction "PB2/PCINT2/SCK/ADC1/T0_7") (pintype "bidirectional"))
    )
  )
)
